# Spi_Flash.net
KiCad netlist of a schematic drawn in Altium Designer
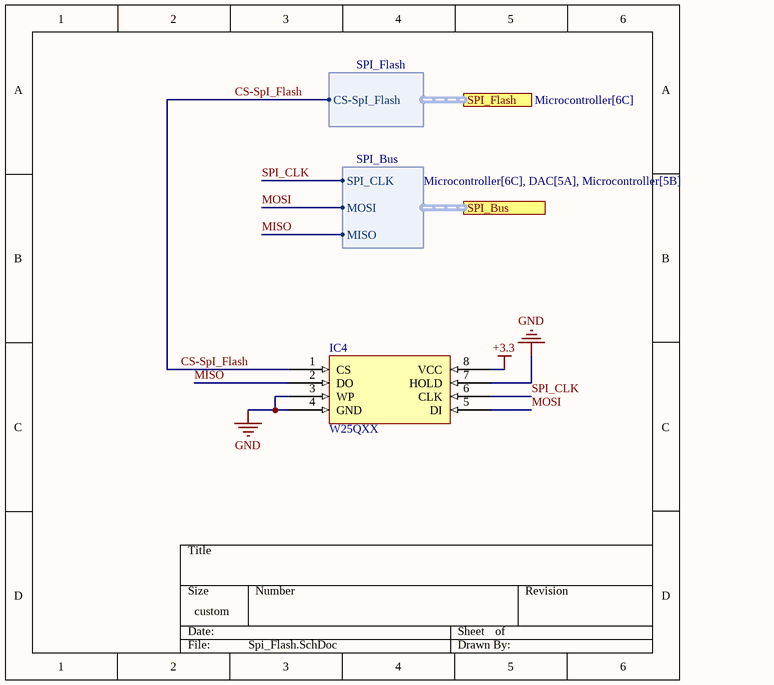
[diagram p0: Spi_Flash.SchDoc]

(export (version "E")
  (design (tool "Eeschema 10.0.6"))
  (components
    (comp (ref "IC4")
      (value "W25QXX")
      (footprint "SOIC-8PIN-280MIL")
      (libsource (lib "kave-eng-pro") (part "w25qxx"))
    )
  )
  (nets
    (net (code "3") (name "+3.3") (class "Default")
      (node (ref "IC4") (pin "8") (pinfunction "VCC_8") (pintype "input"))
    )
    (net (code "4") (name "/CS-SpI_Flash") (class "Default")
      (node (ref "IC4") (pin "1") (pinfunction "CS_1") (pintype "input"))
    )
    (net (code "5") (name "/MISO") (class "Default")
      (node (ref "IC4") (pin "2") (pinfunction "DO_2") (pintype "input"))
    )
    (net (code "6") (name "/MOSI") (class "Default")
      (node (ref "IC4") (pin "5") (pinfunction "DI_5") (pintype "input"))
    )
    (net (code "7") (name "/SPI_CLK") (class "Default")
      (node (ref "IC4") (pin "6") (pinfunction "CLK_6") (pintype "input"))
    )
    (net (code "10") (name "GND") (class "Default")
      (node (ref "IC4") (pin "3") (pinfunction "WP_3") (pintype "input"))
      (node (ref "IC4") (pin "4") (pinfunction "GND_4") (pintype "input"))
      (node (ref "IC4") (pin "7") (pinfunction "HOLD_7") (pintype "input"))
    )
  )
)
